# opt-lasercutter.net
KiCad netlist of a schematic drawn in EAGLE
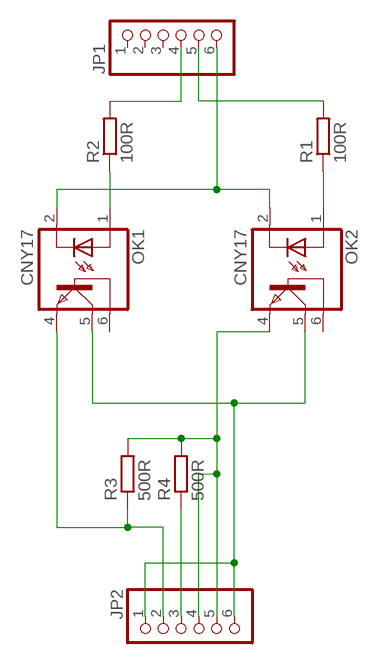
[diagram p0: schematic, sheet 1]

(export (version "E")
  (design (tool "Eeschema 10.0.6"))
  (components
    (comp (ref "JP1")
      (value "PINHD-1X6/90")
      (footprint "eagle-import:1X06_90")
      (libsource (lib "eagle-import") (part "PINHD-1X6/90"))
    )
    (comp (ref "JP2")
      (value "PINHD-1X6/90")
      (footprint "eagle-import:1X06_90")
      (libsource (lib "eagle-import") (part "PINHD-1X6/90"))
    )
    (comp (ref "OK1")
      (value "CNY17")
      (footprint "eagle-import:DIL06")
      (fields (field (name "MPN") "CNY17-1"))
      (libsource (lib "eagle-import") (part "CNY17"))
    )
    (comp (ref "OK2")
      (value "CNY17")
      (footprint "eagle-import:DIL06")
      (fields (field (name "MPN") "CNY17-1"))
      (libsource (lib "eagle-import") (part "CNY17"))
    )
    (comp (ref "R1")
      (value "100R")
      (footprint "eagle-import:0207_7")
      (libsource (lib "eagle-import") (part "R-EU_0207/7"))
    )
    (comp (ref "R2")
      (value "100R")
      (footprint "eagle-import:0207_7")
      (libsource (lib "eagle-import") (part "R-EU_0207/7"))
    )
    (comp (ref "R3")
      (value "500R")
      (footprint "eagle-import:0207_7")
      (libsource (lib "eagle-import") (part "R-EU_0207/7"))
    )
    (comp (ref "R4")
      (value "500R")
      (footprint "eagle-import:0207_7")
      (libsource (lib "eagle-import") (part "R-EU_0207/7"))
    )
  )
  (nets
    (net (code "1") (name "Net-(JP1-Pad4)") (class "Default")
      (node (ref "JP1") (pin "4") (pinfunction "4_4") (pintype "passive"))
      (node (ref "R2") (pin "2") (pinfunction "2_2") (pintype "passive"))
    )
    (net (code "2") (name "Net-(JP1-Pad5)") (class "Default")
      (node (ref "JP1") (pin "5") (pinfunction "5_5") (pintype "passive"))
      (node (ref "R1") (pin "2") (pinfunction "2_2") (pintype "passive"))
    )
    (net (code "3") (name "Net-(JP2-Pad3)") (class "Default")
      (node (ref "JP2") (pin "3") (pinfunction "3_3") (pintype "passive"))
      (node (ref "R4") (pin "1") (pinfunction "1_1") (pintype "passive"))
    )
    (net (code "4") (name "Net-(OK1-A)") (class "Default")
      (node (ref "OK1") (pin "1") (pinfunction "A_1") (pintype "passive"))
      (node (ref "R2") (pin "1") (pinfunction "1_1") (pintype "passive"))
    )
    (net (code "5") (name "Net-(OK1-C)") (class "Default")
      (node (ref "JP1") (pin "6") (pinfunction "6_6") (pintype "passive"))
      (node (ref "OK1") (pin "2") (pinfunction "C_2") (pintype "passive"))
      (node (ref "OK2") (pin "2") (pinfunction "C_2") (pintype "passive"))
    )
    (net (code "6") (name "Net-(OK1-COL)") (class "Default")
      (node (ref "JP2") (pin "1") (pinfunction "1_1") (pintype "passive"))
      (node (ref "JP2") (pin "6") (pinfunction "6_6") (pintype "passive"))
      (node (ref "OK1") (pin "5") (pinfunction "COL_5") (pintype "passive"))
      (node (ref "OK2") (pin "5") (pinfunction "COL_5") (pintype "passive"))
    )
    (net (code "7") (name "Net-(OK1-EMI)") (class "Default")
      (node (ref "JP2") (pin "2") (pinfunction "2_2") (pintype "passive"))
      (node (ref "OK1") (pin "4") (pinfunction "EMI_4") (pintype "passive"))
      (node (ref "R3") (pin "1") (pinfunction "1_1") (pintype "passive"))
    )
    (net (code "8") (name "Net-(OK2-A)") (class "Default")
      (node (ref "OK2") (pin "1") (pinfunction "A_1") (pintype "passive"))
      (node (ref "R1") (pin "1") (pinfunction "1_1") (pintype "passive"))
    )
    (net (code "9") (name "Net-(OK2-EMI)") (class "Default")
      (node (ref "JP2") (pin "4") (pinfunction "4_4") (pintype "passive"))
      (node (ref "JP2") (pin "5") (pinfunction "5_5") (pintype "passive"))
      (node (ref "OK2") (pin "4") (pinfunction "EMI_4") (pintype "passive"))
      (node (ref "R3") (pin "2") (pinfunction "2_2") (pintype "passive"))
      (node (ref "R4") (pin "2") (pinfunction "2_2") (pintype "passive"))
    )
    (net (code "10") (name "unconnected-(JP1-Pad1)") (class "Default")
      (node (ref "JP1") (pin "1") (pinfunction "1_1") (pintype "passive"))
    )
    (net (code "11") (name "unconnected-(JP1-Pad2)") (class "Default")
      (node (ref "JP1") (pin "2") (pinfunction "2_2") (pintype "passive"))
    )
    (net (code "12") (name "unconnected-(JP1-Pad3)") (class "Default")
      (node (ref "JP1") (pin "3") (pinfunction "3_3") (pintype "passive"))
    )
    (net (code "13") (name "unconnected-(OK1-BAS-Pad6)") (class "Default")
      (node (ref "OK1") (pin "6") (pinfunction "BAS_6") (pintype "passive"))
    )
    (net (code "14") (name "unconnected-(OK2-BAS-Pad6)") (class "Default")
      (node (ref "OK2") (pin "6") (pinfunction "BAS_6") (pintype "passive"))
    )
  )
)
